# RecifierBox.net
KiCad netlist of a schematic drawn in EAGLE
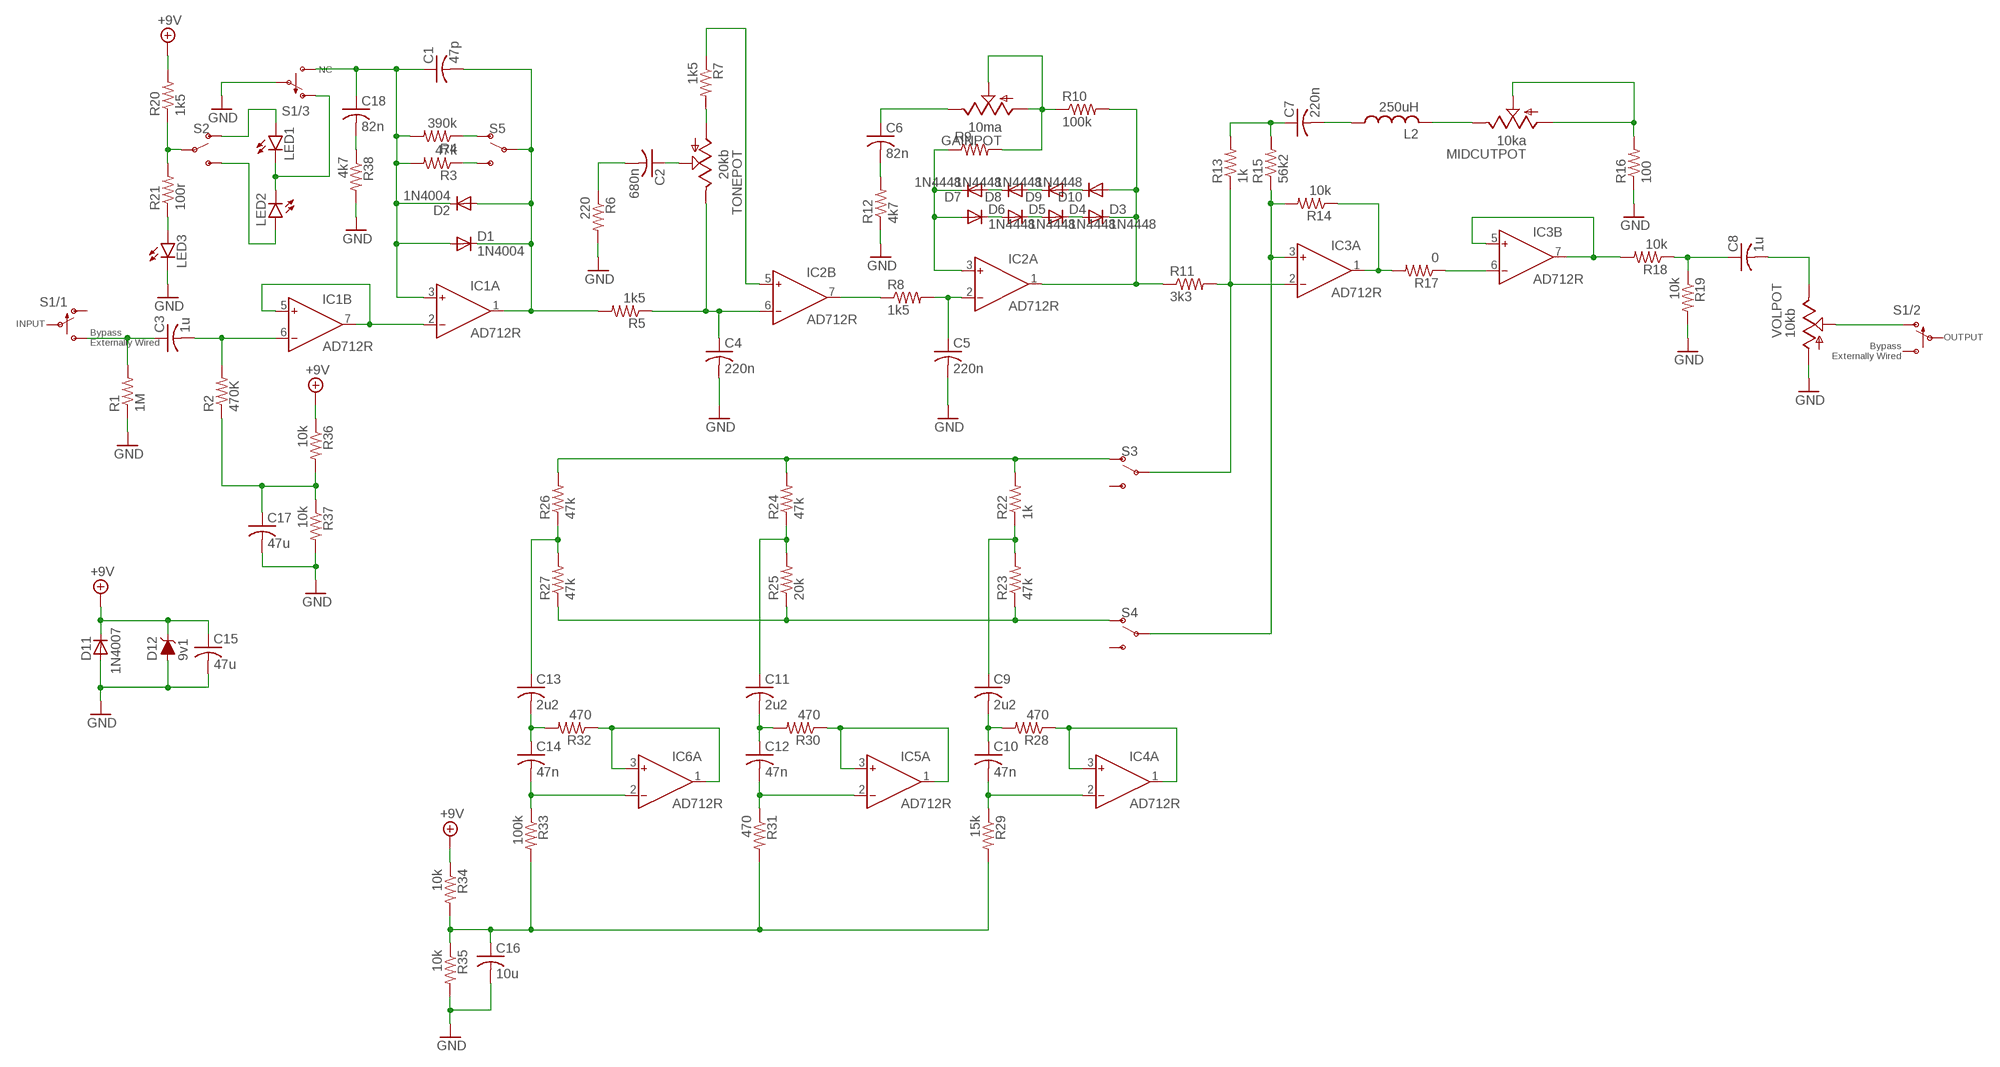
[diagram p0: schematic, sheet 1]

(export (version "E")
  (design (tool "Eeschema 10.0.6"))
  (components
    (comp (ref "C1")
      (value "47p")
      (footprint "eagle-import:C0603")
      (libsource (lib "eagle-import") (part "C-USC0603"))
    )
    (comp (ref "C2")
      (value "680n")
      (footprint "eagle-import:C0603")
      (libsource (lib "eagle-import") (part "C-USC0603"))
    )
    (comp (ref "C3")
      (value "1u")
      (footprint "eagle-import:C0603")
      (libsource (lib "eagle-import") (part "C-USC0603"))
    )
    (comp (ref "C4")
      (value "220n")
      (footprint "eagle-import:C0603")
      (libsource (lib "eagle-import") (part "C-USC0603"))
    )
    (comp (ref "C5")
      (value "220n")
      (footprint "eagle-import:C0603")
      (libsource (lib "eagle-import") (part "C-USC0603"))
    )
    (comp (ref "C6")
      (value "82n")
      (footprint "eagle-import:C0603")
      (libsource (lib "eagle-import") (part "C-USC0603"))
    )
    (comp (ref "C7")
      (value "220n")
      (footprint "eagle-import:C0603")
      (libsource (lib "eagle-import") (part "C-USC0603"))
    )
    (comp (ref "C8")
      (value "1u")
      (footprint "eagle-import:C0603")
      (libsource (lib "eagle-import") (part "C-USC0603"))
    )
    (comp (ref "C9")
      (value "2u2")
      (footprint "eagle-import:C0603")
      (libsource (lib "eagle-import") (part "C-USC0603"))
    )
    (comp (ref "C10")
      (value "47n")
      (footprint "eagle-import:C0603")
      (libsource (lib "eagle-import") (part "C-USC0603"))
    )
    (comp (ref "C11")
      (value "2u2")
      (footprint "eagle-import:C0603")
      (libsource (lib "eagle-import") (part "C-USC0603"))
    )
    (comp (ref "C12")
      (value "47n")
      (footprint "eagle-import:C0603")
      (libsource (lib "eagle-import") (part "C-USC0603"))
    )
    (comp (ref "C13")
      (value "2u2")
      (footprint "eagle-import:C0603")
      (libsource (lib "eagle-import") (part "C-USC0603"))
    )
    (comp (ref "C14")
      (value "47n")
      (footprint "eagle-import:C0603")
      (libsource (lib "eagle-import") (part "C-USC0603"))
    )
    (comp (ref "C15")
      (value "47u")
      (footprint "eagle-import:C050-025X075")
      (libsource (lib "eagle-import") (part "C-US050-025X075"))
    )
    (comp (ref "C16")
      (value "10u")
      (footprint "eagle-import:C0603")
      (libsource (lib "eagle-import") (part "C-USC0603"))
    )
    (comp (ref "C17")
      (value "47u")
      (footprint "eagle-import:C050-025X075")
      (libsource (lib "eagle-import") (part "C-US050-025X075"))
    )
    (comp (ref "C18")
      (value "82n")
      (footprint "eagle-import:C0603")
      (libsource (lib "eagle-import") (part "C-USC0603"))
    )
    (comp (ref "D1")
      (value "1N4004")
      (footprint "eagle-import:DO41-10")
      (libsource (lib "eagle-import") (part "1N4004"))
    )
    (comp (ref "D2")
      (value "1N4004")
      (footprint "eagle-import:DO41-10")
      (libsource (lib "eagle-import") (part "1N4004"))
    )
    (comp (ref "D3")
      (value "1N4448")
      (footprint "eagle-import:DO41-10")
      (libsource (lib "eagle-import") (part "1N4004"))
    )
    (comp (ref "D4")
      (value "1N4448")
      (footprint "eagle-import:DO41-10")
      (libsource (lib "eagle-import") (part "1N4004"))
    )
    (comp (ref "D5")
      (value "1N4448")
      (footprint "eagle-import:DO41-10")
      (libsource (lib "eagle-import") (part "1N4004"))
    )
    (comp (ref "D6")
      (value "1N4448")
      (footprint "eagle-import:DO41-10")
      (libsource (lib "eagle-import") (part "1N4004"))
    )
    (comp (ref "D7")
      (value "1N4448")
      (footprint "eagle-import:DO41-10")
      (libsource (lib "eagle-import") (part "1N4004"))
    )
    (comp (ref "D8")
      (value "1N4448")
      (footprint "eagle-import:DO41-10")
      (libsource (lib "eagle-import") (part "1N4004"))
    )
    (comp (ref "D9")
      (value "1N4448")
      (footprint "eagle-import:DO41-10")
      (libsource (lib "eagle-import") (part "1N4004"))
    )
    (comp (ref "D10")
      (value "1N4448")
      (footprint "eagle-import:DO41-10")
      (libsource (lib "eagle-import") (part "1N4004"))
    )
    (comp (ref "D11")
      (value "1N4007")
      (footprint "eagle-import:DO41-10")
      (libsource (lib "eagle-import") (part "1N4004"))
    )
    (comp (ref "D12")
      (value "9v1")
      (footprint "eagle-import:SOD-323")
      (libsource (lib "eagle-import") (part "DIODE-ZENER-BZT52C3V6S"))
    )
    (comp (ref "GAIN")
      (value "10ma")
      (footprint "eagle-import:THUMBWHEEL")
      (libsource (lib "eagle-import") (part "THUMBPOT"))
    )
    (comp (ref "IC1")
      (value "AD712R")
      (footprint "eagle-import:SO8")
      (fields (field (name "MF") "ALTERA CORPORATION") (field (name "MPN") "AD712KRZ"))
      (libsource (lib "eagle-import") (part "AD712R"))
    )
    (comp (ref "IC2")
      (value "AD712R")
      (footprint "eagle-import:SO8")
      (fields (field (name "MF") "ALTERA CORPORATION") (field (name "MPN") "AD712KRZ"))
      (libsource (lib "eagle-import") (part "AD712R"))
    )
    (comp (ref "IC3")
      (value "AD712R")
      (footprint "eagle-import:SO8")
      (fields (field (name "MF") "ALTERA CORPORATION") (field (name "MPN") "AD712KRZ"))
      (libsource (lib "eagle-import") (part "AD712R"))
    )
    (comp (ref "IC4")
      (value "AD712R")
      (footprint "eagle-import:SO8")
      (fields (field (name "MF") "ALTERA CORPORATION") (field (name "MPN") "AD712KRZ"))
      (libsource (lib "eagle-import") (part "AD712R"))
    )
    (comp (ref "IC5")
      (value "AD712R")
      (footprint "eagle-import:SO8")
      (fields (field (name "MF") "ALTERA CORPORATION") (field (name "MPN") "AD712KRZ"))
      (libsource (lib "eagle-import") (part "AD712R"))
    )
    (comp (ref "IC6")
      (value "AD712R")
      (footprint "eagle-import:SO8")
      (fields (field (name "MF") "ALTERA CORPORATION") (field (name "MPN") "AD712KRZ"))
      (libsource (lib "eagle-import") (part "AD712R"))
    )
    (comp (ref "L2")
      (value "250uH")
      (footprint "eagle-import:0204_5")
      (libsource (lib "eagle-import") (part "L-US0204/5"))
    )
    (comp (ref "LED1")
      (value "LED3MM")
      (footprint "eagle-import:LED3MM")
      (libsource (lib "eagle-import") (part "LED3MM"))
    )
    (comp (ref "LED2")
      (value "LED3MM")
      (footprint "eagle-import:LED3MM")
      (libsource (lib "eagle-import") (part "LED3MM"))
    )
    (comp (ref "LED3")
      (value "LED3MM")
      (footprint "eagle-import:LED3MM")
      (libsource (lib "eagle-import") (part "LED3MM"))
    )
    (comp (ref "MIDCUT")
      (value "10ka")
      (footprint "eagle-import:THUMBWHEEL")
      (libsource (lib "eagle-import") (part "THUMBPOT"))
    )
    (comp (ref "R1")
      (value "1M")
      (footprint "eagle-import:R0603")
      (libsource (lib "eagle-import") (part "R-US_R0603"))
    )
    (comp (ref "R2")
      (value "470K")
      (footprint "eagle-import:R0603")
      (libsource (lib "eagle-import") (part "R-US_R0603"))
    )
    (comp (ref "R3")
      (value "47k")
      (footprint "eagle-import:R0603")
      (libsource (lib "eagle-import") (part "R-US_R0603"))
    )
    (comp (ref "R4")
      (value "390k")
      (footprint "eagle-import:R0603")
      (libsource (lib "eagle-import") (part "R-US_R0603"))
    )
    (comp (ref "R5")
      (value "1k5")
      (footprint "eagle-import:R0603")
      (libsource (lib "eagle-import") (part "R-US_R0603"))
    )
    (comp (ref "R6")
      (value "220")
      (footprint "eagle-import:R0603")
      (libsource (lib "eagle-import") (part "R-US_R0603"))
    )
    (comp (ref "R7")
      (value "1k5")
      (footprint "eagle-import:R0603")
      (libsource (lib "eagle-import") (part "R-US_R0603"))
    )
    (comp (ref "R8")
      (value "1k5")
      (footprint "eagle-import:R0603")
      (libsource (lib "eagle-import") (part "R-US_R0603"))
    )
    (comp (ref "R9")
      (value "R-US_R0603")
      (footprint "eagle-import:R0603")
      (libsource (lib "eagle-import") (part "R-US_R0603"))
    )
    (comp (ref "R10")
      (value "100k")
      (footprint "eagle-import:R0603")
      (libsource (lib "eagle-import") (part "R-US_R0603"))
    )
    (comp (ref "R11")
      (value "3k3")
      (footprint "eagle-import:R0603")
      (libsource (lib "eagle-import") (part "R-US_R0603"))
    )
    (comp (ref "R12")
      (value "4k7")
      (footprint "eagle-import:R0603")
      (libsource (lib "eagle-import") (part "R-US_R0603"))
    )
    (comp (ref "R13")
      (value "1k")
      (footprint "eagle-import:R0603")
      (libsource (lib "eagle-import") (part "R-US_R0603"))
    )
    (comp (ref "R14")
      (value "10k")
      (footprint "eagle-import:R0603")
      (libsource (lib "eagle-import") (part "R-US_R0603"))
    )
    (comp (ref "R15")
      (value "56k2")
      (footprint "eagle-import:R0603")
      (libsource (lib "eagle-import") (part "R-US_R0603"))
    )
    (comp (ref "R16")
      (value "100")
      (footprint "eagle-import:R0603")
      (libsource (lib "eagle-import") (part "R-US_R0603"))
    )
    (comp (ref "R17")
      (value "0")
      (footprint "eagle-import:R0603")
      (libsource (lib "eagle-import") (part "R-US_R0603"))
    )
    (comp (ref "R18")
      (value "10k")
      (footprint "eagle-import:R0603")
      (libsource (lib "eagle-import") (part "R-US_R0603"))
    )
    (comp (ref "R19")
      (value "10k")
      (footprint "eagle-import:R0603")
      (libsource (lib "eagle-import") (part "R-US_R0603"))
    )
    (comp (ref "R20")
      (value "1k5")
      (footprint "eagle-import:R0603")
      (libsource (lib "eagle-import") (part "R-US_R0603"))
    )
    (comp (ref "R21")
      (value "100r")
      (footprint "eagle-import:R0603")
      (libsource (lib "eagle-import") (part "R-US_R0603"))
    )
    (comp (ref "R22")
      (value "1k")
      (footprint "eagle-import:R0603")
      (libsource (lib "eagle-import") (part "R-US_R0603"))
    )
    (comp (ref "R23")
      (value "47k")
      (footprint "eagle-import:R0603")
      (libsource (lib "eagle-import") (part "R-US_R0603"))
    )
    (comp (ref "R24")
      (value "47k")
      (footprint "eagle-import:R0603")
      (libsource (lib "eagle-import") (part "R-US_R0603"))
    )
    (comp (ref "R25")
      (value "20k")
      (footprint "eagle-import:R0603")
      (libsource (lib "eagle-import") (part "R-US_R0603"))
    )
    (comp (ref "R26")
      (value "47k")
      (footprint "eagle-import:R0603")
      (libsource (lib "eagle-import") (part "R-US_R0603"))
    )
    (comp (ref "R27")
      (value "47k")
      (footprint "eagle-import:R0603")
      (libsource (lib "eagle-import") (part "R-US_R0603"))
    )
    (comp (ref "R28")
      (value "470")
      (footprint "eagle-import:R0603")
      (libsource (lib "eagle-import") (part "R-US_R0603"))
    )
    (comp (ref "R29")
      (value "15k")
      (footprint "eagle-import:R0603")
      (libsource (lib "eagle-import") (part "R-US_R0603"))
    )
    (comp (ref "R30")
      (value "470")
      (footprint "eagle-import:R0603")
      (libsource (lib "eagle-import") (part "R-US_R0603"))
    )
    (comp (ref "R31")
      (value "470")
      (footprint "eagle-import:R0603")
      (libsource (lib "eagle-import") (part "R-US_R0603"))
    )
    (comp (ref "R32")
      (value "470")
      (footprint "eagle-import:R0603")
      (libsource (lib "eagle-import") (part "R-US_R0603"))
    )
    (comp (ref "R33")
      (value "100k")
      (footprint "eagle-import:R0603")
      (libsource (lib "eagle-import") (part "R-US_R0603"))
    )
    (comp (ref "R34")
      (value "10k")
      (footprint "eagle-import:R0603")
      (libsource (lib "eagle-import") (part "R-US_R0603"))
    )
    (comp (ref "R35")
      (value "10k")
      (footprint "eagle-import:R0603")
      (libsource (lib "eagle-import") (part "R-US_R0603"))
    )
    (comp (ref "R36")
      (value "10k")
      (footprint "eagle-import:R0603")
      (libsource (lib "eagle-import") (part "R-US_R0603"))
    )
    (comp (ref "R37")
      (value "10k")
      (footprint "eagle-import:R0603")
      (libsource (lib "eagle-import") (part "R-US_R0603"))
    )
    (comp (ref "R38")
      (value "4k7")
      (footprint "eagle-import:R0603")
      (libsource (lib "eagle-import") (part "R-US_R0603"))
    )
    (comp (ref "S1")
      (value "SWITCH-3DPT-INLINE-BREAKOUT-BYPASS")
      (footprint "eagle-import:1X04")
      (libsource (lib "eagle-import") (part "SWITCH-3DPT-INLINE-BREAKOUT-BYPASS"))
    )
    (comp (ref "S2")
      (value "SWITCH-SPDT-PTH-11.6X4.0MM")
      (footprint "eagle-import:SWITCH_SPDT_PTH_11.6X4.0MM")
      (libsource (lib "eagle-import") (part "SWITCH-SPDT-PTH-11.6X4.0MM"))
    )
    (comp (ref "S3")
      (value "SWITCH-SPDT-PTH-11.6X4.0MM")
      (footprint "eagle-import:SWITCH_SPDT_PTH_11.6X4.0MM")
      (libsource (lib "eagle-import") (part "SWITCH-SPDT-PTH-11.6X4.0MM"))
    )
    (comp (ref "S4")
      (value "SWITCH-SPDT-PTH-11.6X4.0MM")
      (footprint "eagle-import:SWITCH_SPDT_PTH_11.6X4.0MM")
      (libsource (lib "eagle-import") (part "SWITCH-SPDT-PTH-11.6X4.0MM"))
    )
    (comp (ref "S5")
      (value "SWITCH-SPDT-PTH-11.6X4.0MM")
      (footprint "eagle-import:SWITCH_SPDT_PTH_11.6X4.0MM")
      (libsource (lib "eagle-import") (part "SWITCH-SPDT-PTH-11.6X4.0MM"))
    )
    (comp (ref "TONE")
      (value "20kb")
      (footprint "eagle-import:THUMBWHEEL")
      (libsource (lib "eagle-import") (part "THUMBPOT"))
    )
    (comp (ref "VOL")
      (value "10kb")
      (footprint "eagle-import:THUMBWHEEL")
      (libsource (lib "eagle-import") (part "THUMBPOT"))
    )
  )
  (nets
    (net (code "1") (name "+9V") (class "Default")
      (node (ref "C15") (pin "1") (pinfunction "1_1") (pintype "passive"))
      (node (ref "D11") (pin "C") (pinfunction "C_C") (pintype "passive"))
      (node (ref "D12") (pin "C") (pinfunction "C_C") (pintype "passive"))
      (node (ref "R20") (pin "2") (pinfunction "2_2") (pintype "passive"))
      (node (ref "R34") (pin "1") (pinfunction "1_1") (pintype "passive"))
      (node (ref "R36") (pin "1") (pinfunction "1_1") (pintype "passive"))
    )
    (net (code "2") (name "GND") (class "Default")
      (node (ref "C15") (pin "2") (pinfunction "2_2") (pintype "passive"))
      (node (ref "C16") (pin "2") (pinfunction "2_2") (pintype "passive"))
      (node (ref "C17") (pin "2") (pinfunction "2_2") (pintype "passive"))
      (node (ref "C4") (pin "2") (pinfunction "2_2") (pintype "passive"))
      (node (ref "C5") (pin "2") (pinfunction "2_2") (pintype "passive"))
      (node (ref "D11") (pin "A") (pinfunction "A_A") (pintype "passive"))
      (node (ref "D12") (pin "A") (pinfunction "A_A") (pintype "passive"))
      (node (ref "LED3") (pin "K") (pinfunction "C_K") (pintype "passive"))
      (node (ref "R1") (pin "1") (pinfunction "1_1") (pintype "passive"))
      (node (ref "R12") (pin "1") (pinfunction "1_1") (pintype "passive"))
      (node (ref "R16") (pin "1") (pinfunction "1_1") (pintype "passive"))
      (node (ref "R19") (pin "2") (pinfunction "2_2") (pintype "passive"))
      (node (ref "R35") (pin "2") (pinfunction "2_2") (pintype "passive"))
      (node (ref "R37") (pin "2") (pinfunction "2_2") (pintype "passive"))
      (node (ref "R38") (pin "2") (pinfunction "2_2") (pintype "passive"))
      (node (ref "R6") (pin "2") (pinfunction "2_2") (pintype "passive"))
      (node (ref "S1") (pin "3") (pinfunction "COMMON_3") (pintype "passive"))
      (node (ref "VOL") (pin "1") (pinfunction "A_1") (pintype "passive"))
    )
    (net (code "3") (name "Net-(C2-Pad2)") (class "Default")
      (node (ref "C2") (pin "2") (pinfunction "2_2") (pintype "passive"))
      (node (ref "R6") (pin "1") (pinfunction "1_1") (pintype "passive"))
    )
    (net (code "4") (name "Net-(C3-Pad1)") (class "Default")
      (node (ref "C3") (pin "1") (pinfunction "1_1") (pintype "passive"))
      (node (ref "R1") (pin "2") (pinfunction "2_2") (pintype "passive"))
    )
    (net (code "5") (name "Net-(C6-Pad2)") (class "Default")
      (node (ref "C6") (pin "2") (pinfunction "2_2") (pintype "passive"))
      (node (ref "R12") (pin "2") (pinfunction "2_2") (pintype "passive"))
    )
    (net (code "6") (name "Net-(C7-Pad1)") (class "Default")
      (node (ref "C7") (pin "1") (pinfunction "1_1") (pintype "passive"))
      (node (ref "R13") (pin "2") (pinfunction "2_2") (pintype "passive"))
      (node (ref "R15") (pin "2") (pinfunction "2_2") (pintype "passive"))
    )
    (net (code "7") (name "Net-(C7-Pad2)") (class "Default")
      (node (ref "C7") (pin "2") (pinfunction "2_2") (pintype "passive"))
      (node (ref "L2") (pin "1") (pinfunction "1_1") (pintype "passive"))
    )
    (net (code "8") (name "Net-(C8-Pad1)") (class "Default")
      (node (ref "C8") (pin "1") (pinfunction "1_1") (pintype "passive"))
      (node (ref "R18") (pin "1") (pinfunction "1_1") (pintype "passive"))
      (node (ref "R19") (pin "1") (pinfunction "1_1") (pintype "passive"))
    )
    (net (code "9") (name "Net-(C9-Pad1)") (class "Default")
      (node (ref "C9") (pin "1") (pinfunction "1_1") (pintype "passive"))
      (node (ref "R22") (pin "1") (pinfunction "1_1") (pintype "passive"))
      (node (ref "R23") (pin "2") (pinfunction "2_2") (pintype "passive"))
    )
    (net (code "10") (name "Net-(C10-Pad1)") (class "Default")
      (node (ref "C10") (pin "1") (pinfunction "1_1") (pintype "passive"))
      (node (ref "C9") (pin "2") (pinfunction "2_2") (pintype "passive"))
      (node (ref "R28") (pin "2") (pinfunction "2_2") (pintype "passive"))
    )
    (net (code "11") (name "Net-(C11-Pad1)") (class "Default")
      (node (ref "C11") (pin "1") (pinfunction "1_1") (pintype "passive"))
      (node (ref "R24") (pin "1") (pinfunction "1_1") (pintype "passive"))
      (node (ref "R25") (pin "2") (pinfunction "2_2") (pintype "passive"))
    )
    (net (code "12") (name "Net-(C11-Pad2)") (class "Default")
      (node (ref "C11") (pin "2") (pinfunction "2_2") (pintype "passive"))
      (node (ref "C12") (pin "1") (pinfunction "1_1") (pintype "passive"))
      (node (ref "R30") (pin "2") (pinfunction "2_2") (pintype "passive"))
    )
    (net (code "13") (name "Net-(C13-Pad1)") (class "Default")
      (node (ref "C13") (pin "1") (pinfunction "1_1") (pintype "passive"))
      (node (ref "R26") (pin "1") (pinfunction "1_1") (pintype "passive"))
      (node (ref "R27") (pin "2") (pinfunction "2_2") (pintype "passive"))
    )
    (net (code "14") (name "Net-(C13-Pad2)") (class "Default")
      (node (ref "C13") (pin "2") (pinfunction "2_2") (pintype "passive"))
      (node (ref "C14") (pin "1") (pinfunction "1_1") (pintype "passive"))
      (node (ref "R32") (pin "2") (pinfunction "2_2") (pintype "passive"))
    )
    (net (code "15") (name "Net-(C16-Pad1)") (class "Default")
      (node (ref "C16") (pin "1") (pinfunction "1_1") (pintype "passive"))
      (node (ref "R29") (pin "2") (pinfunction "2_2") (pintype "passive"))
      (node (ref "R31") (pin "2") (pinfunction "2_2") (pintype "passive"))
      (node (ref "R33") (pin "2") (pinfunction "2_2") (pintype "passive"))
      (node (ref "R34") (pin "2") (pinfunction "2_2") (pintype "passive"))
      (node (ref "R35") (pin "1") (pinfunction "1_1") (pintype "passive"))
    )
    (net (code "16") (name "Net-(C17-Pad1)") (class "Default")
      (node (ref "C17") (pin "1") (pinfunction "1_1") (pintype "passive"))
      (node (ref "R2") (pin "1") (pinfunction "1_1") (pintype "passive"))
      (node (ref "R36") (pin "2") (pinfunction "2_2") (pintype "passive"))
      (node (ref "R37") (pin "1") (pinfunction "1_1") (pintype "passive"))
    )
    (net (code "17") (name "Net-(C18-Pad2)") (class "Default")
      (node (ref "C18") (pin "2") (pinfunction "2_2") (pintype "passive"))
      (node (ref "R38") (pin "1") (pinfunction "1_1") (pintype "passive"))
    )
    (net (code "18") (name "Net-(D3-PadA)") (class "Default")
      (node (ref "D3") (pin "A") (pinfunction "A_A") (pintype "passive"))
      (node (ref "D4") (pin "C") (pinfunction "C_C") (pintype "passive"))
    )
    (net (code "19") (name "Net-(D4-PadA)") (class "Default")
      (node (ref "D4") (pin "A") (pinfunction "A_A") (pintype "passive"))
      (node (ref "D5") (pin "C") (pinfunction "C_C") (pintype "passive"))
    )
    (net (code "20") (name "Net-(D5-PadA)") (class "Default")
      (node (ref "D5") (pin "A") (pinfunction "A_A") (pintype "passive"))
      (node (ref "D6") (pin "C") (pinfunction "C_C") (pintype "passive"))
    )
    (net (code "21") (name "Net-(D7-PadA)") (class "Default")
      (node (ref "D7") (pin "A") (pinfunction "A_A") (pintype "passive"))
      (node (ref "D8") (pin "C") (pinfunction "C_C") (pintype "passive"))
    )
    (net (code "22") (name "Net-(D8-PadA)") (class "Default")
      (node (ref "D8") (pin "A") (pinfunction "A_A") (pintype "passive"))
      (node (ref "D9") (pin "C") (pinfunction "C_C") (pintype "passive"))
    )
    (net (code "23") (name "Net-(D10-PadC)") (class "Default")
      (node (ref "D10") (pin "C") (pinfunction "C_C") (pintype "passive"))
      (node (ref "D9") (pin "A") (pinfunction "A_A") (pintype "passive"))
    )
    (net (code "24") (name "Net-(GAINA-A)") (class "Default")
      (node (ref "GAIN") (pin "1") (pinfunction "A_1") (pintype "passive"))
      (node (ref "GAIN") (pin "2") (pinfunction "S_2") (pintype "passive"))
      (node (ref "R10") (pin "1") (pinfunction "1_1") (pintype "passive"))
      (node (ref "R9") (pin "2") (pinfunction "2_2") (pintype "passive"))
    )
    (net (code "25") (name "Net-(GAINA-E)") (class "Default")
      (node (ref "C6") (pin "1") (pinfunction "1_1") (pintype "passive"))
      (node (ref "GAIN") (pin "3") (pinfunction "E_3") (pintype "passive"))
    )
    (net (code "26") (name "Net-(IC1A-IN+)") (class "Default")
      (node (ref "C1") (pin "1") (pinfunction "1_1") (pintype "passive"))
      (node (ref "C18") (pin "1") (pinfunction "1_1") (pintype "passive"))
      (node (ref "D1") (pin "A") (pinfunction "A_A") (pintype "passive"))
      (node (ref "D2") (pin "C") (pinfunction "C_C") (pintype "passive"))
      (node (ref "IC1") (pin "3") (pinfunction "IN+_3") (pintype "input"))
      (node (ref "R3") (pin "2") (pinfunction "2_2") (pintype "passive"))
      (node (ref "R4") (pin "2") (pinfunction "2_2") (pintype "passive"))
    )
    (net (code "27") (name "Net-(IC1A-IN-)") (class "Default")
      (node (ref "IC1") (pin "2") (pinfunction "IN-_2") (pintype "input"))
      (node (ref "IC1") (pin "5") (pinfunction "IN+_5") (pintype "input"))
      (node (ref "IC1") (pin "7") (pinfunction "OUT_7") (pintype "output"))
    )
    (net (code "28") (name "Net-(IC1A-OUT)") (class "Default")
      (node (ref "C1") (pin "2") (pinfunction "2_2") (pintype "passive"))
      (node (ref "D1") (pin "C") (pinfunction "C_C") (pintype "passive"))
      (node (ref "D2") (pin "A") (pinfunction "A_A") (pintype "passive"))
      (node (ref "IC1") (pin "1") (pinfunction "OUT_1") (pintype "output"))
      (node (ref "R5") (pin "2") (pinfunction "2_2") (pintype "passive"))
      (node (ref "S5") (pin "2") (pinfunction "P_2") (pintype "passive"))
    )
    (net (code "29") (name "Net-(IC1B-IN-)") (class "Default")
      (node (ref "C3") (pin "2") (pinfunction "2_2") (pintype "passive"))
      (node (ref "IC1") (pin "6") (pinfunction "IN-_6") (pintype "input"))
      (node (ref "R2") (pin "2") (pinfunction "2_2") (pintype "passive"))
    )
    (net (code "30") (name "Net-(IC2A-IN+)") (class "Default")
      (node (ref "D6") (pin "A") (pinfunction "A_A") (pintype "passive"))
      (node (ref "D7") (pin "C") (pinfunction "C_C") (pintype "passive"))
      (node (ref "IC2") (pin "3") (pinfunction "IN+_3") (pintype "input"))
      (node (ref "R9") (pin "1") (pinfunction "1_1") (pintype "passive"))
    )
    (net (code "31") (name "Net-(IC2A-IN-)") (class "Default")
      (node (ref "C5") (pin "1") (pinfunction "1_1") (pintype "passive"))
      (node (ref "IC2") (pin "2") (pinfunction "IN-_2") (pintype "input"))
      (node (ref "R8") (pin "2") (pinfunction "2_2") (pintype "passive"))
    )
    (net (code "32") (name "Net-(IC2A-OUT)") (class "Default")
      (node (ref "D10") (pin "A") (pinfunction "A_A") (pintype "passive"))
      (node (ref "D3") (pin "C") (pinfunction "C_C") (pintype "passive"))
      (node (ref "IC2") (pin "1") (pinfunction "OUT_1") (pintype "output"))
      (node (ref "R10") (pin "2") (pinfunction "2_2") (pintype "passive"))
      (node (ref "R11") (pin "1") (pinfunction "1_1") (pintype "passive"))
    )
    (net (code "33") (name "Net-(IC2B-IN+)") (class "Default")
      (node (ref "IC2") (pin "5") (pinfunction "IN+_5") (pintype "input"))
      (node (ref "R7") (pin "1") (pinfunction "1_1") (pintype "passive"))
    )
    (net (code "34") (name "Net-(IC2B-IN-)") (class "Default")
      (node (ref "C4") (pin "1") (pinfunction "1_1") (pintype "passive"))
      (node (ref "IC2") (pin "6") (pinfunction "IN-_6") (pintype "input"))
      (node (ref "R5") (pin "1") (pinfunction "1_1") (pintype "passive"))
      (node (ref "TONE") (pin "3") (pinfunction "E_3") (pintype "passive"))
    )
    (net (code "35") (name "Net-(IC2B-OUT)") (class "Default")
      (node (ref "IC2") (pin "7") (pinfunction "OUT_7") (pintype "output"))
      (node (ref "R8") (pin "1") (pinfunction "1_1") (pintype "passive"))
    )
    (net (code "36") (name "Net-(IC3A-IN+)") (class "Default")
      (node (ref "IC3") (pin "3") (pinfunction "IN+_3") (pintype "input"))
      (node (ref "R14") (pin "2") (pinfunction "2_2") (pintype "passive"))
      (node (ref "R15") (pin "1") (pinfunction "1_1") (pintype "passive"))
      (node (ref "S4") (pin "2") (pinfunction "P_2") (pintype "passive"))
    )
    (net (code "37") (name "Net-(IC3A-IN-)") (class "Default")
      (node (ref "IC3") (pin "2") (pinfunction "IN-_2") (pintype "input"))
      (node (ref "R11") (pin "2") (pinfunction "2_2") (pintype "passive"))
      (node (ref "R13") (pin "1") (pinfunction "1_1") (pintype "passive"))
      (node (ref "S3") (pin "2") (pinfunction "P_2") (pintype "passive"))
    )
    (net (code "38") (name "Net-(IC3A-OUT)") (class "Default")
      (node (ref "IC3") (pin "1") (pinfunction "OUT_1") (pintype "output"))
      (node (ref "R14") (pin "1") (pinfunction "1_1") (pintype "passive"))
      (node (ref "R17") (pin "2") (pinfunction "2_2") (pintype "passive"))
    )
    (net (code "39") (name "Net-(IC3B-IN+)") (class "Default")
      (node (ref "IC3") (pin "5") (pinfunction "IN+_5") (pintype "input"))
      (node (ref "IC3") (pin "7") (pinfunction "OUT_7") (pintype "output"))
      (node (ref "R18") (pin "2") (pinfunction "2_2") (pintype "passive"))
    )
    (net (code "40") (name "Net-(IC3B-IN-)") (class "Default")
      (node (ref "IC3") (pin "6") (pinfunction "IN-_6") (pintype "input"))
      (node (ref "R17") (pin "1") (pinfunction "1_1") (pintype "passive"))
    )
    (net (code "41") (name "Net-(IC4A-IN+)") (class "Default")
      (node (ref "IC4") (pin "1") (pinfunction "OUT_1") (pintype "output"))
      (node (ref "IC4") (pin "3") (pinfunction "IN+_3") (pintype "input"))
      (node (ref "R28") (pin "1") (pinfunction "1_1") (pintype "passive"))
    )
    (net (code "42") (name "Net-(IC4A-IN-)") (class "Default")
      (node (ref "C10") (pin "2") (pinfunction "2_2") (pintype "passive"))
      (node (ref "IC4") (pin "2") (pinfunction "IN-_2") (pintype "input"))
      (node (ref "R29") (pin "1") (pinfunction "1_1") (pintype "passive"))
    )
    (net (code "43") (name "Net-(IC5A-IN+)") (class "Default")
      (node (ref "IC5") (pin "1") (pinfunction "OUT_1") (pintype "output"))
      (node (ref "IC5") (pin "3") (pinfunction "IN+_3") (pintype "input"))
      (node (ref "R30") (pin "1") (pinfunction "1_1") (pintype "passive"))
    )
    (net (code "44") (name "Net-(IC5A-IN-)") (class "Default")
      (node (ref "C12") (pin "2") (pinfunction "2_2") (pintype "passive"))
      (node (ref "IC5") (pin "2") (pinfunction "IN-_2") (pintype "input"))
      (node (ref "R31") (pin "1") (pinfunction "1_1") (pintype "passive"))
    )
    (net (code "45") (name "Net-(IC6A-IN+)") (class "Default")
      (node (ref "IC6") (pin "1") (pinfunction "OUT_1") (pintype "output"))
      (node (ref "IC6") (pin "3") (pinfunction "IN+_3") (pintype "input"))
      (node (ref "R32") (pin "1") (pinfunction "1_1") (pintype "passive"))
    )
    (net (code "46") (name "Net-(IC6A-IN-)") (class "Default")
      (node (ref "C14") (pin "2") (pinfunction "2_2") (pintype "passive"))
      (node (ref "IC6") (pin "2") (pinfunction "IN-_2") (pintype "input"))
      (node (ref "R33") (pin "1") (pinfunction "1_1") (pintype "passive"))
    )
    (net (code "47") (name "Net-(LED1-C)") (class "Default")
      (node (ref "LED1") (pin "K") (pinfunction "C_K") (pintype "passive"))
      (node (ref "LED2") (pin "K") (pinfunction "C_K") (pintype "passive"))
      (node (ref "S1") (pin "4") (pinfunction "NORMALLY-ON_4") (pintype "passive"))
    )
    (net (code "48") (name "Net-(LED3-PadA)") (class "Default")
      (node (ref "LED3") (pin "A") (pinfunction "A_A") (pintype "passive"))
      (node (ref "R21") (pin "1") (pinfunction "1_1") (pintype "passive"))
    )
    (net (code "49") (name "Net-(MIDCUTA-A)") (class "Default")
      (node (ref "MIDCUT") (pin "1") (pinfunction "A_1") (pintype "passive"))
      (node (ref "MIDCUT") (pin "2") (pinfunction "S_2") (pintype "passive"))
      (node (ref "R16") (pin "2") (pinfunction "2_2") (pintype "passive"))
    )
    (net (code "50") (name "Net-(MIDCUTA-E)") (class "Default")
      (node (ref "L2") (pin "2") (pinfunction "2_2") (pintype "passive"))
      (node (ref "MIDCUT") (pin "3") (pinfunction "E_3") (pintype "passive"))
    )
    (net (code "51") (name "Net-(S1B-NORMALLY-ON)") (class "Default")
      (node (ref "S1") (pin "2") (pinfunction "NORMALLY-ON_2") (pintype "passive"))
      (node (ref "VOL") (pin "2") (pinfunction "S_2") (pintype "passive"))
    )
    (net (code "52") (name "Net-(S2-O)") (class "Default")
      (node (ref "LED1") (pin "A") (pinfunction "A_A") (pintype "passive"))
      (node (ref "S2") (pin "1") (pinfunction "O_1") (pintype "passive"))
    )
    (net (code "53") (name "Net-(S2-P)") (class "Default")
      (node (ref "R20") (pin "1") (pinfunction "1_1") (pintype "passive"))
      (node (ref "R21") (pin "2") (pinfunction "2_2") (pintype "passive"))
      (node (ref "S2") (pin "2") (pinfunction "P_2") (pintype "passive"))
    )
    (net (code "54") (name "Net-(S2-S)") (class "Default")
      (node (ref "LED2") (pin "A") (pinfunction "A_A") (pintype "passive"))
      (node (ref "S2") (pin "3") (pinfunction "S_3") (pintype "passive"))
    )
    (net (code "55") (name "Net-(S3-O)") (class "Default")
      (node (ref "R22") (pin "2") (pinfunction "2_2") (pintype "passive"))
      (node (ref "R24") (pin "2") (pinfunction "2_2") (pintype "passive"))
      (node (ref "R26") (pin "2") (pinfunction "2_2") (pintype "passive"))
      (node (ref "S3") (pin "1") (pinfunction "O_1") (pintype "passive"))
    )
    (net (code "56") (name "Net-(S4-O)") (class "Default")
      (node (ref "R23") (pin "1") (pinfunction "1_1") (pintype "passive"))
      (node (ref "R25") (pin "1") (pinfunction "1_1") (pintype "passive"))
      (node (ref "R27") (pin "1") (pinfunction "1_1") (pintype "passive"))
      (node (ref "S4") (pin "1") (pinfunction "O_1") (pintype "passive"))
    )
    (net (code "57") (name "Net-(S5-O)") (class "Default")
      (node (ref "R4") (pin "1") (pinfunction "1_1") (pintype "passive"))
      (node (ref "S5") (pin "1") (pinfunction "O_1") (pintype "passive"))
    )
    (net (code "58") (name "Net-(S5-S)") (class "Default")
      (node (ref "R3") (pin "1") (pinfunction "1_1") (pintype "passive"))
      (node (ref "S5") (pin "3") (pinfunction "S_3") (pintype "passive"))
    )
    (net (code "59") (name "Net-(TONEA-A)") (class "Default")
      (node (ref "R7") (pin "2") (pinfunction "2_2") (pintype "passive"))
      (node (ref "TONE") (pin "1") (pinfunction "A_1") (pintype "passive"))
    )
    (net (code "60") (name "Net-(TONEA-S)") (class "Default")
      (node (ref "C2") (pin "1") (pinfunction "1_1") (pintype "passive"))
      (node (ref "TONE") (pin "2") (pinfunction "S_2") (pintype "passive"))
    )
    (net (code "61") (name "Net-(VOLA-E)") (class "Default")
      (node (ref "C8") (pin "2") (pinfunction "2_2") (pintype "passive"))
      (node (ref "VOL") (pin "3") (pinfunction "E_3") (pintype "passive"))
    )
    (net (code "62") (name "unconnected-(S1A-NORMALLY-ON-Pad1)") (class "Default")
      (node (ref "S1") (pin "1") (pinfunction "NORMALLY-ON_1") (pintype "passive"))
    )
    (net (code "63") (name "unconnected-(S3-S-Pad3)") (class "Default")
      (node (ref "S3") (pin "3") (pinfunction "S_3") (pintype "passive"))
    )
    (net (code "64") (name "unconnected-(S4-S-Pad3)") (class "Default")
      (node (ref "S4") (pin "3") (pinfunction "S_3") (pintype "passive"))
    )
  )
)
